# nguyenly.net
KiCad netlist of a schematic drawn in Altium Designer
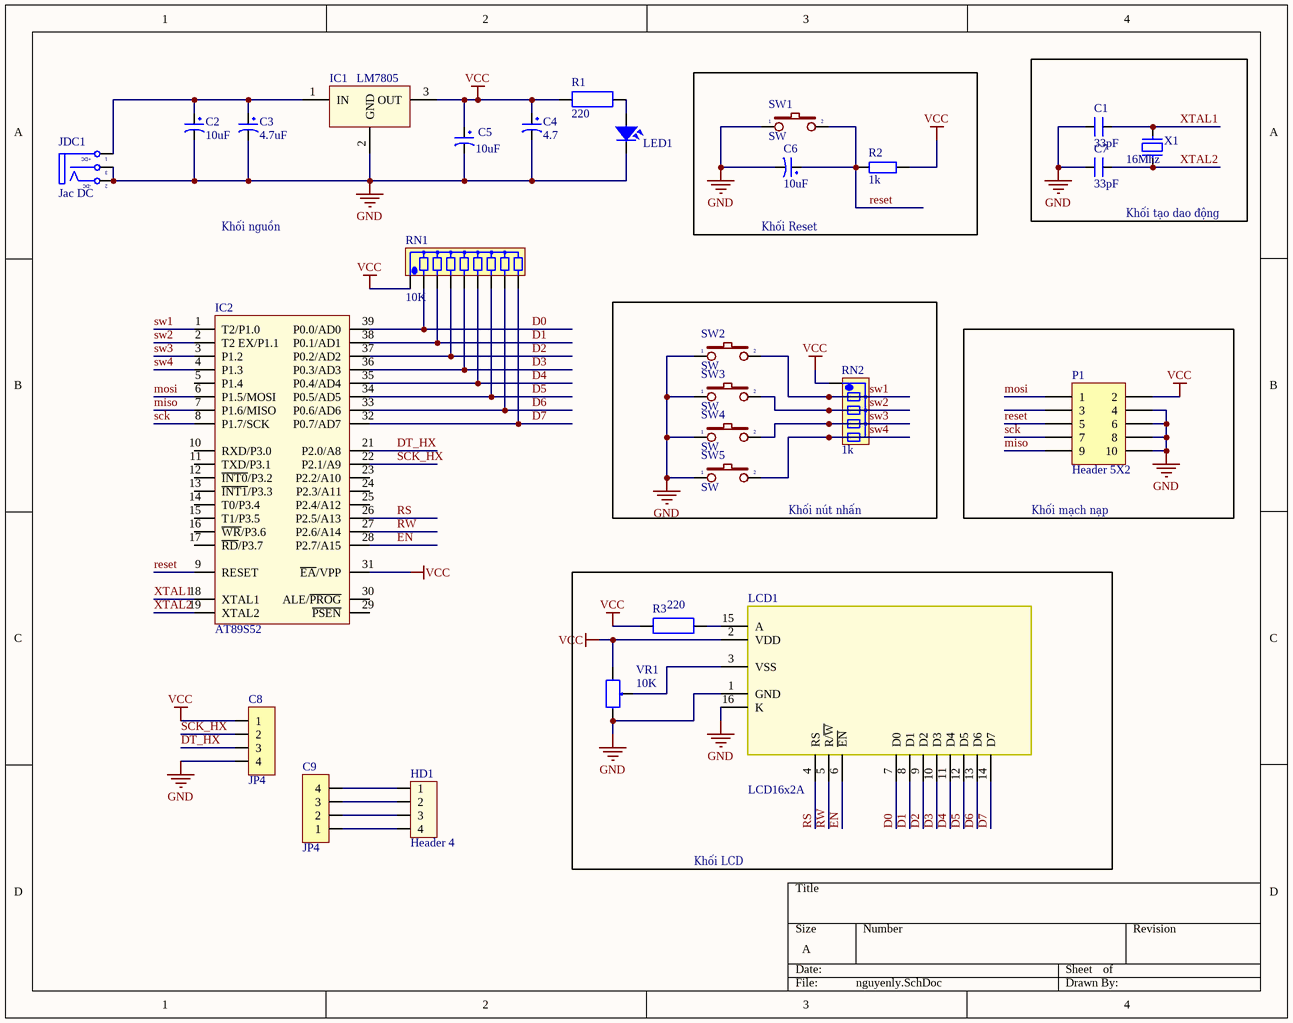
[diagram p0: nguyenly.SchDoc]

(export (version "E")
  (design (tool "Eeschema 10.0.6"))
  (components
    (comp (ref "C1")
      (value "33pF")
      (footprint "CN1")
      (description "Cap np  1pF - 472pF")
      (libsource (lib "echipkool-com-library") (part "CN1"))
    )
    (comp (ref "C2")
      (value "10uF")
      (footprint "CP1/2")
      (description "Cap P  0,1uF < 22uF , 16 - 50V")
      (libsource (lib "echipkool-com-library") (part "CP1"))
    )
    (comp (ref "C3")
      (value "4.7uF")
      (footprint "CP1/2")
      (description "Cap P  0,1uF < 22uF , 16 - 50V")
      (libsource (lib "echipkool-com-library") (part "CP1"))
    )
    (comp (ref "C4")
      (value "4.7")
      (footprint "CP1/2")
      (description "Cap P  0,1uF < 22uF , 16 - 50V")
      (libsource (lib "echipkool-com-library") (part "CP1"))
    )
    (comp (ref "C5")
      (value "10uF")
      (footprint "CP1/2")
      (description "Cap P  0,1uF < 22uF , 16 - 50V")
      (libsource (lib "echipkool-com-library") (part "CP1"))
    )
    (comp (ref "C6")
      (value "10uF")
      (footprint "CP1/2")
      (description "Cap P  0,1uF < 22uF , 16 - 50V")
      (libsource (lib "") (part "CP1_1"))
    )
    (comp (ref "C7")
      (value "33pF")
      (footprint "CN1")
      (description "Cap np  1pF - 472pF")
      (libsource (lib "echipkool-com-library") (part "CN1"))
    )
    (comp (ref "C8")
      (value "JP4")
      (footprint "JP4-C1C")
      (description "WR-PHD 2.54 mm Angled Socket Header")
      (fields
        (field (name "MANUFACTURER") "Würth Elektronik eiSos GmbH")
        (field (name "PARTNO") "613004143121")
        (field (name "CREATED BY") "Karrer Zheng")
      )
      (libsource (lib "My Library") (part "JP4"))
    )
    (comp (ref "C9")
      (value "JP4")
      (footprint "JP4-C1C")
      (description "WR-PHD 2.54 mm Angled Socket Header")
      (fields
        (field (name "MANUFACTURER") "Würth Elektronik eiSos GmbH")
        (field (name "PARTNO") "613004143121")
        (field (name "CREATED BY") "Karrer Zheng")
      )
      (libsource (lib "") (part "JP4_1"))
    )
    (comp (ref "HD1")
      (value "Header 4")
      (footprint "HED4")
      (description "Header 4 (Green)")
      (libsource (lib "syhaunguyen") (part "Hed4"))
    )
    (comp (ref "IC1")
      (value "LM7805")
      (footprint "QTO-220")
      (description "On ap +, from + 5 to + 24VDC")
      (libsource (lib "syhaunguyen") (part "LM78xx"))
    )
    (comp (ref "IC2")
      (value "AT89S52")
      (footprint "DIP40/W0.6")
      (description "AT89S52, 8k Byte Flash Memory , 40 Pin")
      (libsource (lib "My Library") (part "AT89S52"))
    )
    (comp (ref "JDC1")
      (value "Jac DC")
      (footprint "DC-IN")
      (description "Jac DC input")
      (libsource (lib "syhaunguyen") (part "DCIN"))
    )
    (comp (ref "LCD1")
      (value "LCD16x2A")
      (footprint "LCD16X2")
      (description "LCD dipslay 16 char, 2 line")
      (libsource (lib "syhaunguyen") (part "LCD16x2"))
    )
    (comp (ref "LED1")
      (value "LED")
      (footprint "LED-3")
      (description "LED Single colour Green and Red")
      (libsource (lib "syhaunguyen") (part "LED"))
    )
    (comp (ref "P1")
      (value "Header 5X2")
      (footprint "HDR2X5")
      (description "Header, 5-Pin, Dual row")
      (fields (field (name "PUBLISHER") "Altium Limited"))
      (libsource (lib "Cty1") (part "Header 5X2"))
    )
    (comp (ref "R1")
      (value "220")
      (footprint "R1W")
      (description "Resistor 1W")
      (libsource (lib "echipkool-com-library") (part "R1W"))
    )
    (comp (ref "R2")
      (value "1k")
      (footprint "R1/4W")
      (description "Resistor 1/4W")
      (libsource (lib "syhaunguyen") (part "R1/4W"))
    )
    (comp (ref "R3")
      (value "220")
      (footprint "R1W")
      (description "Resistor 1W")
      (libsource (lib "echipkool-com-library") (part "R1W"))
    )
    (comp (ref "RN1")
      (value "10K")
      (footprint "RN8")
      (description "Resistor 8 (Thanh)")
      (libsource (lib "syhaunguyen") (part "RN8"))
    )
    (comp (ref "RN2")
      (value "1k")
      (footprint "RN4")
      (description "Resistor 4 (thanh)")
      (libsource (lib "syhaunguyen") (part "RN4"))
    )
    (comp (ref "SW1")
      (value "SW")
      (footprint "SW2")
      (description "Switch button 2 pin")
      (libsource (lib "syhaunguyen") (part "SW2"))
    )
    (comp (ref "SW2")
      (value "SW")
      (footprint "SW2")
      (description "Switch button 2 pin")
      (libsource (lib "syhaunguyen") (part "SW2"))
    )
    (comp (ref "SW3")
      (value "SW")
      (footprint "SW2")
      (description "Switch button 2 pin")
      (libsource (lib "syhaunguyen") (part "SW2"))
    )
    (comp (ref "SW4")
      (value "SW")
      (footprint "SW2")
      (description "Switch button 2 pin")
      (libsource (lib "syhaunguyen") (part "SW2"))
    )
    (comp (ref "SW5")
      (value "SW")
      (footprint "SW2")
      (description "Switch button 2 pin")
      (libsource (lib "syhaunguyen") (part "SW2"))
    )
    (comp (ref "VR1")
      (value "10K")
      (footprint "VR")
      (description "Var Resistor")
      (libsource (lib "syhaunguyen") (part "VR"))
    )
    (comp (ref "X1")
      (value "16Mhz")
      (footprint "XT2")
      (description "Crystal For all Crystal 2pin.")
      (libsource (lib "syhaunguyen") (part "XT2"))
    )
  )
  (nets
    (net (code "1") (name "/D0") (class "Default")
      (node (ref "IC2") (pin "39") (pinfunction "P0.0/AD0_39") (pintype "passive"))
      (node (ref "LCD1") (pin "7") (pinfunction "D0_7") (pintype "passive"))
      (node (ref "RN1") (pin "2") (pinfunction "2_2") (pintype "passive"))
    )
    (net (code "2") (name "/D1") (class "Default")
      (node (ref "IC2") (pin "38") (pinfunction "P0.1/AD1_38") (pintype "passive"))
      (node (ref "LCD1") (pin "8") (pinfunction "D1_8") (pintype "passive"))
      (node (ref "RN1") (pin "3") (pinfunction "3_3") (pintype "passive"))
    )
    (net (code "3") (name "/D2") (class "Default")
      (node (ref "IC2") (pin "37") (pinfunction "P0.2/AD2_37") (pintype "passive"))
      (node (ref "LCD1") (pin "9") (pinfunction "D2_9") (pintype "passive"))
      (node (ref "RN1") (pin "4") (pinfunction "4_4") (pintype "passive"))
    )
    (net (code "4") (name "/D3") (class "Default")
      (node (ref "IC2") (pin "36") (pinfunction "P0.3/AD3_36") (pintype "passive"))
      (node (ref "LCD1") (pin "10") (pinfunction "D3_10") (pintype "passive"))
      (node (ref "RN1") (pin "5") (pinfunction "5_5") (pintype "passive"))
    )
    (net (code "5") (name "/D4") (class "Default")
      (node (ref "IC2") (pin "35") (pinfunction "P0.4/AD4_35") (pintype "passive"))
      (node (ref "LCD1") (pin "11") (pinfunction "D4_11") (pintype "passive"))
      (node (ref "RN1") (pin "6") (pinfunction "6_6") (pintype "passive"))
    )
    (net (code "6") (name "/D5") (class "Default")
      (node (ref "IC2") (pin "34") (pinfunction "P0.5/AD5_34") (pintype "passive"))
      (node (ref "LCD1") (pin "12") (pinfunction "D5_12") (pintype "passive"))
      (node (ref "RN1") (pin "7") (pinfunction "7_7") (pintype "passive"))
    )
    (net (code "7") (name "/D6") (class "Default")
      (node (ref "IC2") (pin "33") (pinfunction "P0.6/AD6_33") (pintype "passive"))
      (node (ref "LCD1") (pin "13") (pinfunction "D6_13") (pintype "passive"))
      (node (ref "RN1") (pin "8") (pinfunction "8_8") (pintype "passive"))
    )
    (net (code "8") (name "/D7") (class "Default")
      (node (ref "IC2") (pin "32") (pinfunction "P0.7/AD7_32") (pintype "passive"))
      (node (ref "LCD1") (pin "14") (pinfunction "D7_14") (pintype "passive"))
      (node (ref "RN1") (pin "9") (pinfunction "9_9") (pintype "passive"))
    )
    (net (code "9") (name "/DT_HX") (class "Default")
      (node (ref "C8") (pin "3") (pinfunction "3_3") (pintype "passive"))
      (node (ref "IC2") (pin "21") (pinfunction "P2.0/A8_21") (pintype "passive"))
    )
    (net (code "10") (name "/EN") (class "Default")
      (node (ref "IC2") (pin "28") (pinfunction "P2.7/A15_28") (pintype "passive"))
      (node (ref "LCD1") (pin "6") (pinfunction "~{EN}_6") (pintype "passive"))
    )
    (net (code "11") (name "/RS") (class "Default")
      (node (ref "IC2") (pin "26") (pinfunction "P2.5/A13_26") (pintype "passive"))
      (node (ref "LCD1") (pin "4") (pinfunction "RS_4") (pintype "passive"))
    )
    (net (code "12") (name "/RW") (class "Default")
      (node (ref "IC2") (pin "27") (pinfunction "P2.6/A14_27") (pintype "passive"))
      (node (ref "LCD1") (pin "5") (pinfunction "R/~{W}_5") (pintype "passive"))
    )
    (net (code "13") (name "/SCK_HX") (class "Default")
      (node (ref "C8") (pin "2") (pinfunction "2_2") (pintype "passive"))
      (node (ref "IC2") (pin "22") (pinfunction "P2.1/A9_22") (pintype "passive"))
    )
    (net (code "14") (name "/XTAL1") (class "Default")
      (node (ref "C1") (pin "2") (pinfunction "2_2") (pintype "passive"))
      (node (ref "IC2") (pin "18") (pinfunction "XTAL1_18") (pintype "passive"))
      (node (ref "X1") (pin "1") (pinfunction "1_1") (pintype "passive"))
    )
    (net (code "15") (name "/XTAL2") (class "Default")
      (node (ref "C7") (pin "2") (pinfunction "2_2") (pintype "passive"))
      (node (ref "IC2") (pin "19") (pinfunction "XTAL2_19") (pintype "passive"))
      (node (ref "X1") (pin "2") (pinfunction "2_2") (pintype "passive"))
    )
    (net (code "16") (name "/miso") (class "Default")
      (node (ref "IC2") (pin "7") (pinfunction "P1.6/MISO_7") (pintype "passive"))
      (node (ref "P1") (pin "9") (pinfunction "9_9") (pintype "passive"))
    )
    (net (code "17") (name "/mosi") (class "Default")
      (node (ref "IC2") (pin "6") (pinfunction "P1.5/MOSI_6") (pintype "passive"))
      (node (ref "P1") (pin "1") (pinfunction "1_1") (pintype "passive"))
    )
    (net (code "18") (name "/reset") (class "Default")
      (node (ref "C6") (pin "1") (pinfunction "1_1") (pintype "passive"))
      (node (ref "IC2") (pin "9") (pinfunction "RESET_9") (pintype "passive"))
      (node (ref "P1") (pin "5") (pinfunction "5_5") (pintype "passive"))
      (node (ref "R2") (pin "1") (pinfunction "1_1") (pintype "passive"))
      (node (ref "SW1") (pin "2") (pinfunction "2_2") (pintype "passive"))
    )
    (net (code "19") (name "/sck") (class "Default")
      (node (ref "IC2") (pin "8") (pinfunction "P1.7/SCK_8") (pintype "passive"))
      (node (ref "P1") (pin "7") (pinfunction "7_7") (pintype "passive"))
    )
    (net (code "20") (name "/sw1") (class "Default")
      (node (ref "IC2") (pin "1") (pinfunction "T2/P1.0_1") (pintype "passive"))
      (node (ref "RN2") (pin "2") (pinfunction "2_2") (pintype "passive"))
      (node (ref "SW2") (pin "2") (pinfunction "2_2") (pintype "passive"))
    )
    (net (code "21") (name "/sw2") (class "Default")
      (node (ref "IC2") (pin "2") (pinfunction "T2_EX/P1.1_2") (pintype "passive"))
      (node (ref "RN2") (pin "3") (pinfunction "3_3") (pintype "passive"))
      (node (ref "SW3") (pin "2") (pinfunction "2_2") (pintype "passive"))
    )
    (net (code "22") (name "/sw3") (class "Default")
      (node (ref "IC2") (pin "3") (pinfunction "P1.2_3") (pintype "passive"))
      (node (ref "RN2") (pin "4") (pinfunction "4_4") (pintype "passive"))
      (node (ref "SW4") (pin "2") (pinfunction "2_2") (pintype "passive"))
    )
    (net (code "23") (name "/sw4") (class "Default")
      (node (ref "IC2") (pin "4") (pinfunction "P1.3_4") (pintype "passive"))
      (node (ref "RN2") (pin "5") (pinfunction "5_5") (pintype "passive"))
      (node (ref "SW5") (pin "2") (pinfunction "2_2") (pintype "passive"))
    )
    (net (code "24") (name "GND") (class "Default")
      (node (ref "C1") (pin "1") (pinfunction "1_1") (pintype "passive"))
      (node (ref "C2") (pin "2") (pinfunction "2_2") (pintype "passive"))
      (node (ref "C3") (pin "2") (pinfunction "2_2") (pintype "passive"))
      (node (ref "C4") (pin "2") (pinfunction "2_2") (pintype "passive"))
      (node (ref "C5") (pin "2") (pinfunction "2_2") (pintype "passive"))
      (node (ref "C6") (pin "2") (pinfunction "2_2") (pintype "passive"))
      (node (ref "C7") (pin "1") (pinfunction "1_1") (pintype "passive"))
      (node (ref "C8") (pin "4") (pinfunction "4_4") (pintype "passive"))
      (node (ref "IC1") (pin "2") (pinfunction "GND_2") (pintype "passive"))
      (node (ref "IC2") (pin "20") (pinfunction "GND_20") (pintype "power_in"))
      (node (ref "JDC1") (pin "2") (pinfunction "TN_2") (pintype "passive"))
      (node (ref "JDC1") (pin "3") (pinfunction "S_3") (pintype "power_in"))
      (node (ref "LCD1") (pin "1") (pinfunction "GND_1") (pintype "passive"))
      (node (ref "LCD1") (pin "16") (pinfunction "K_16") (pintype "passive"))
      (node (ref "LED1") (pin "2") (pinfunction "2_2") (pintype "passive"))
      (node (ref "P1") (pin "10") (pinfunction "10_10") (pintype "passive"))
      (node (ref "P1") (pin "4") (pinfunction "4_4") (pintype "passive"))
      (node (ref "P1") (pin "6") (pinfunction "6_6") (pintype "passive"))
      (node (ref "P1") (pin "8") (pinfunction "8_8") (pintype "passive"))
      (node (ref "SW1") (pin "1") (pinfunction "1_1") (pintype "passive"))
      (node (ref "SW2") (pin "1") (pinfunction "1_1") (pintype "passive"))
      (node (ref "SW3") (pin "1") (pinfunction "1_1") (pintype "passive"))
      (node (ref "SW4") (pin "1") (pinfunction "1_1") (pintype "passive"))
      (node (ref "SW5") (pin "1") (pinfunction "1_1") (pintype "passive"))
      (node (ref "VR1") (pin "3") (pinfunction "3_3") (pintype "passive"))
    )
    (net (code "25") (name "Net-(C9-Pad1)") (class "Default")
      (node (ref "C9") (pin "1") (pinfunction "1_1") (pintype "passive"))
      (node (ref "HD1") (pin "4") (pinfunction "4_4") (pintype "passive"))
    )
    (net (code "26") (name "Net-(C9-Pad2)") (class "Default")
      (node (ref "C9") (pin "2") (pinfunction "2_2") (pintype "passive"))
      (node (ref "HD1") (pin "3") (pinfunction "3_3") (pintype "passive"))
    )
    (net (code "27") (name "Net-(C9-Pad3)") (class "Default")
      (node (ref "C9") (pin "3") (pinfunction "3_3") (pintype "passive"))
      (node (ref "HD1") (pin "2") (pinfunction "2_2") (pintype "passive"))
    )
    (net (code "28") (name "Net-(C9-Pad4)") (class "Default")
      (node (ref "C9") (pin "4") (pinfunction "4_4") (pintype "passive"))
      (node (ref "HD1") (pin "1") (pinfunction "1_1") (pintype "passive"))
    )
    (net (code "29") (name "Net-(IC1-IN)") (class "Default")
      (node (ref "C2") (pin "1") (pinfunction "1_1") (pintype "passive"))
      (node (ref "C3") (pin "1") (pinfunction "1_1") (pintype "passive"))
      (node (ref "IC1") (pin "1") (pinfunction "IN_1") (pintype "passive"))
      (node (ref "JDC1") (pin "1") (pinfunction "T_1") (pintype "passive"))
    )
    (net (code "30") (name "Net-(LCD1-A)") (class "Default")
      (node (ref "LCD1") (pin "15") (pinfunction "A_15") (pintype "passive"))
      (node (ref "R3") (pin "2") (pinfunction "2_2") (pintype "passive"))
    )
    (net (code "31") (name "Net-(LCD1-VSS)") (class "Default")
      (node (ref "LCD1") (pin "3") (pinfunction "VSS_3") (pintype "passive"))
      (node (ref "VR1") (pin "2") (pinfunction "2_2") (pintype "passive"))
    )
    (net (code "32") (name "Net-(LED1-Pad1)") (class "Default")
      (node (ref "LED1") (pin "1") (pinfunction "1_1") (pintype "passive"))
      (node (ref "R1") (pin "2") (pinfunction "2_2") (pintype "passive"))
    )
    (net (code "33") (name "VCC") (class "Default")
      (node (ref "C4") (pin "1") (pinfunction "1_1") (pintype "passive"))
      (node (ref "C5") (pin "1") (pinfunction "1_1") (pintype "passive"))
      (node (ref "C8") (pin "1") (pinfunction "1_1") (pintype "passive"))
      (node (ref "IC1") (pin "3") (pinfunction "OUT_3") (pintype "passive"))
      (node (ref "IC2") (pin "31") (pinfunction "~{EA}/VPP_31") (pintype "passive"))
      (node (ref "IC2") (pin "40") (pinfunction "VCC_40") (pintype "power_in"))
      (node (ref "LCD1") (pin "2") (pinfunction "VDD_2") (pintype "passive"))
      (node (ref "P1") (pin "2") (pinfunction "2_2") (pintype "passive"))
      (node (ref "R1") (pin "1") (pinfunction "1_1") (pintype "passive"))
      (node (ref "R2") (pin "2") (pinfunction "2_2") (pintype "passive"))
      (node (ref "R3") (pin "1") (pinfunction "1_1") (pintype "passive"))
      (node (ref "RN1") (pin "1") (pinfunction "1_1") (pintype "passive"))
      (node (ref "RN2") (pin "1") (pinfunction "1_1") (pintype "passive"))
      (node (ref "VR1") (pin "1") (pinfunction "1_1") (pintype "passive"))
    )
    (net (code "34") (name "unconnected-(IC2-ALE{slash}~{PROG}-Pad30)") (class "Default")
      (node (ref "IC2") (pin "30") (pinfunction "ALE/~{PROG}_30") (pintype "passive"))
    )
    (net (code "35") (name "unconnected-(IC2-P1.4-Pad5)") (class "Default")
      (node (ref "IC2") (pin "5") (pinfunction "P1.4_5") (pintype "passive"))
    )
    (net (code "36") (name "unconnected-(IC2-P2.2{slash}A10-Pad23)") (class "Default")
      (node (ref "IC2") (pin "23") (pinfunction "P2.2/A10_23") (pintype "passive"))
    )
    (net (code "37") (name "unconnected-(IC2-P2.3{slash}A11-Pad24)") (class "Default")
      (node (ref "IC2") (pin "24") (pinfunction "P2.3/A11_24") (pintype "passive"))
    )
    (net (code "38") (name "unconnected-(IC2-P2.4{slash}A12-Pad25)") (class "Default")
      (node (ref "IC2") (pin "25") (pinfunction "P2.4/A12_25") (pintype "passive"))
    )
    (net (code "39") (name "unconnected-(IC2-RXD{slash}P3.0-Pad10)") (class "Default")
      (node (ref "IC2") (pin "10") (pinfunction "RXD/P3.0_10") (pintype "passive"))
    )
    (net (code "40") (name "unconnected-(IC2-T0{slash}P3.4-Pad14)") (class "Default")
      (node (ref "IC2") (pin "14") (pinfunction "T0/P3.4_14") (pintype "passive"))
    )
    (net (code "41") (name "unconnected-(IC2-T1{slash}P3.5-Pad15)") (class "Default")
      (node (ref "IC2") (pin "15") (pinfunction "T1/P3.5_15") (pintype "passive"))
    )
    (net (code "42") (name "unconnected-(IC2-TXD{slash}P3.1-Pad11)") (class "Default")
      (node (ref "IC2") (pin "11") (pinfunction "TXD/P3.1_11") (pintype "passive"))
    )
    (net (code "43") (name "unconnected-(IC2-~{INT0}{slash}P3.2-Pad12)") (class "Default")
      (node (ref "IC2") (pin "12") (pinfunction "~{INT0}/P3.2_12") (pintype "passive"))
    )
    (net (code "44") (name "unconnected-(IC2-~{INT1}{slash}P3.3-Pad13)") (class "Default")
      (node (ref "IC2") (pin "13") (pinfunction "~{INT1}/P3.3_13") (pintype "passive"))
    )
    (net (code "45") (name "unconnected-(IC2-~{PSEN}-Pad29)") (class "Default")
      (node (ref "IC2") (pin "29") (pinfunction "~{PSEN}_29") (pintype "passive"))
    )
    (net (code "46") (name "unconnected-(IC2-~{RD}{slash}P3.7-Pad17)") (class "Default")
      (node (ref "IC2") (pin "17") (pinfunction "~{RD}/P3.7_17") (pintype "passive"))
    )
    (net (code "47") (name "unconnected-(IC2-~{WR}{slash}P3.6-Pad16)") (class "Default")
      (node (ref "IC2") (pin "16") (pinfunction "~{WR}/P3.6_16") (pintype "passive"))
    )
    (net (code "48") (name "unconnected-(P1-Pad3)") (class "Default")
      (node (ref "P1") (pin "3") (pinfunction "3_3") (pintype "passive"))
    )
  )
)
